# Car_0.net
KiCad netlist of a schematic drawn in EAGLE
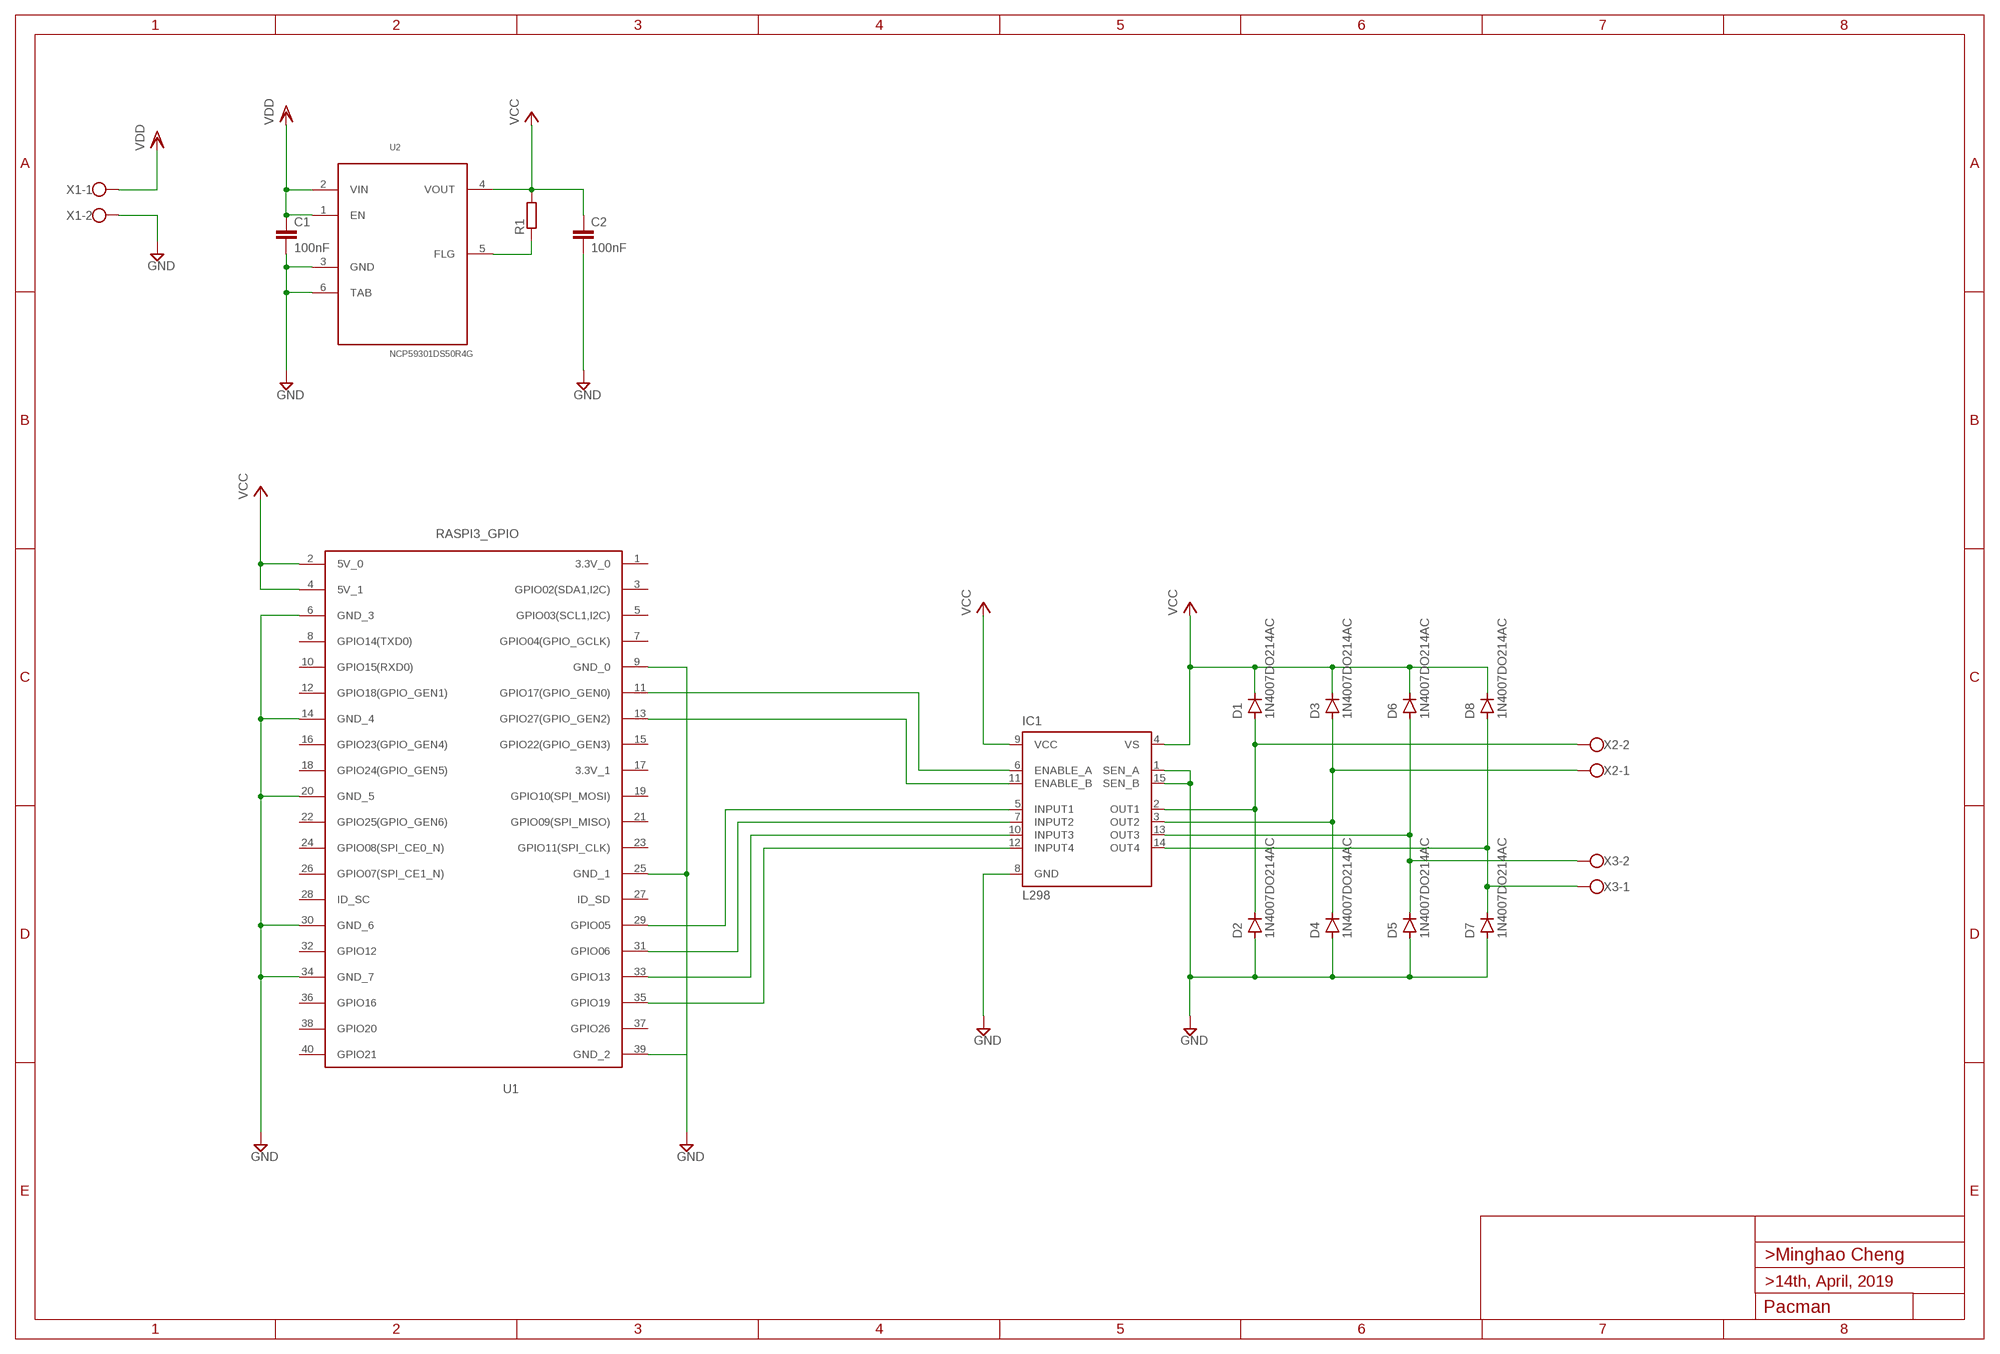
[diagram p0: schematic, sheet 1]

(export (version "E")
  (design (tool "Eeschema 10.0.6"))
  (components
    (comp (ref "C1")
      (value "100nF")
      (footprint "eagle-import:C0805")
      (libsource (lib "eagle-import") (part "C-EUC0805"))
    )
    (comp (ref "C2")
      (value "100nF")
      (footprint "eagle-import:C0805")
      (libsource (lib "eagle-import") (part "C-EUC0805"))
    )
    (comp (ref "D1")
      (value "1N4007DO214AC")
      (footprint "eagle-import:SMA-DO214AC")
      (libsource (lib "eagle-import") (part "1N4007DO214AC"))
    )
    (comp (ref "D2")
      (value "1N4007DO214AC")
      (footprint "eagle-import:SMA-DO214AC")
      (libsource (lib "eagle-import") (part "1N4007DO214AC"))
    )
    (comp (ref "D3")
      (value "1N4007DO214AC")
      (footprint "eagle-import:SMA-DO214AC")
      (libsource (lib "eagle-import") (part "1N4007DO214AC"))
    )
    (comp (ref "D4")
      (value "1N4007DO214AC")
      (footprint "eagle-import:SMA-DO214AC")
      (libsource (lib "eagle-import") (part "1N4007DO214AC"))
    )
    (comp (ref "D5")
      (value "1N4007DO214AC")
      (footprint "eagle-import:SMA-DO214AC")
      (libsource (lib "eagle-import") (part "1N4007DO214AC"))
    )
    (comp (ref "D6")
      (value "1N4007DO214AC")
      (footprint "eagle-import:SMA-DO214AC")
      (libsource (lib "eagle-import") (part "1N4007DO214AC"))
    )
    (comp (ref "D7")
      (value "1N4007DO214AC")
      (footprint "eagle-import:SMA-DO214AC")
      (libsource (lib "eagle-import") (part "1N4007DO214AC"))
    )
    (comp (ref "D8")
      (value "1N4007DO214AC")
      (footprint "eagle-import:SMA-DO214AC")
      (libsource (lib "eagle-import") (part "1N4007DO214AC"))
    )
    (comp (ref "IC1")
      (value "L298")
      (footprint "eagle-import:MULTIWATT-15")
      (fields (field (name "MPN") "L298N"))
      (libsource (lib "eagle-import") (part "L298"))
    )
    (comp (ref "R1")
      (value "R-EU_R0805")
      (footprint "eagle-import:R0805")
      (libsource (lib "eagle-import") (part "R-EU_R0805"))
    )
    (comp (ref "U1")
      (value "RASPI3_GPIO")
      (footprint "eagle-import:FE20-2")
      (libsource (lib "eagle-import") (part "RASPI3_GPIO"))
    )
    (comp (ref "U2")
      (value "NCP59301DS50R4G")
      (footprint "eagle-import:TO263-5")
      (libsource (lib "eagle-import") (part "NCP59301DS50R4G"))
    )
    (comp (ref "X1")
      (value "W237-102")
      (footprint "eagle-import:W237-102")
      (fields (field (name "MPN") "237-102"))
      (libsource (lib "eagle-import") (part "W237-102"))
    )
    (comp (ref "X2")
      (value "W237-102")
      (footprint "eagle-import:W237-102")
      (fields (field (name "MPN") "237-102"))
      (libsource (lib "eagle-import") (part "W237-102"))
    )
    (comp (ref "X3")
      (value "W237-102")
      (footprint "eagle-import:W237-102")
      (fields (field (name "MPN") "237-102"))
      (libsource (lib "eagle-import") (part "W237-102"))
    )
  )
  (nets
    (net (code "1") (name "GND") (class "Default")
      (node (ref "C1") (pin "2") (pinfunction "2_2") (pintype "passive"))
      (node (ref "C2") (pin "2") (pinfunction "2_2") (pintype "passive"))
      (node (ref "D2") (pin "A") (pinfunction "A_A") (pintype "passive"))
      (node (ref "D4") (pin "A") (pinfunction "A_A") (pintype "passive"))
      (node (ref "D5") (pin "A") (pinfunction "A_A") (pintype "passive"))
      (node (ref "D7") (pin "A") (pinfunction "A_A") (pintype "passive"))
      (node (ref "IC1") (pin "1") (pinfunction "SEN_A_1") (pintype "input"))
      (node (ref "IC1") (pin "15") (pinfunction "SEN_B_15") (pintype "input"))
      (node (ref "IC1") (pin "8") (pinfunction "GND_8") (pintype "power_in"))
      (node (ref "U1") (pin "14") (pinfunction "GND_4_14") (pintype "bidirectional"))
      (node (ref "U1") (pin "20") (pinfunction "GND_5_20") (pintype "bidirectional"))
      (node (ref "U1") (pin "25") (pinfunction "GND_1_25") (pintype "bidirectional"))
      (node (ref "U1") (pin "30") (pinfunction "GND_6_30") (pintype "bidirectional"))
      (node (ref "U1") (pin "34") (pinfunction "GND_7_34") (pintype "bidirectional"))
      (node (ref "U1") (pin "39") (pinfunction "GND_2_39") (pintype "bidirectional"))
      (node (ref "U1") (pin "6") (pinfunction "GND_3_6") (pintype "bidirectional"))
      (node (ref "U1") (pin "9") (pinfunction "GND_0_9") (pintype "bidirectional"))
      (node (ref "U2") (pin "3") (pinfunction "GND_3") (pintype "output"))
      (node (ref "U2") (pin "6") (pinfunction "TAB_6") (pintype "output"))
      (node (ref "X1") (pin "2") (pinfunction "KL_2") (pintype "passive"))
    )
    (net (code "2") (name "Net-(D2-C)") (class "Default")
      (node (ref "D1") (pin "A") (pinfunction "A_A") (pintype "passive"))
      (node (ref "D2") (pin "K") (pinfunction "C_K") (pintype "passive"))
      (node (ref "IC1") (pin "2") (pinfunction "OUT1_2") (pintype "output"))
      (node (ref "X2") (pin "2") (pinfunction "KL_2") (pintype "passive"))
    )
    (net (code "3") (name "Net-(D4-C)") (class "Default")
      (node (ref "D3") (pin "A") (pinfunction "A_A") (pintype "passive"))
      (node (ref "D4") (pin "K") (pinfunction "C_K") (pintype "passive"))
      (node (ref "IC1") (pin "3") (pinfunction "OUT2_3") (pintype "output"))
      (node (ref "X2") (pin "1") (pinfunction "KL_1") (pintype "passive"))
    )
    (net (code "4") (name "Net-(D5-C)") (class "Default")
      (node (ref "D5") (pin "K") (pinfunction "C_K") (pintype "passive"))
      (node (ref "D6") (pin "A") (pinfunction "A_A") (pintype "passive"))
      (node (ref "IC1") (pin "13") (pinfunction "OUT3_13") (pintype "output"))
      (node (ref "X3") (pin "2") (pinfunction "KL_2") (pintype "passive"))
    )
    (net (code "5") (name "Net-(D7-C)") (class "Default")
      (node (ref "D7") (pin "K") (pinfunction "C_K") (pintype "passive"))
      (node (ref "D8") (pin "A") (pinfunction "A_A") (pintype "passive"))
      (node (ref "IC1") (pin "14") (pinfunction "OUT4_14") (pintype "output"))
      (node (ref "X3") (pin "1") (pinfunction "KL_1") (pintype "passive"))
    )
    (net (code "6") (name "Net-(IC1-ENABLE_A)") (class "Default")
      (node (ref "IC1") (pin "6") (pinfunction "ENABLE_A_6") (pintype "input"))
      (node (ref "U1") (pin "11") (pinfunction "GPIO17(GPIO_GEN0)_11") (pintype "bidirectional"))
    )
    (net (code "7") (name "Net-(IC1-ENABLE_B)") (class "Default")
      (node (ref "IC1") (pin "11") (pinfunction "ENABLE_B_11") (pintype "input"))
      (node (ref "U1") (pin "13") (pinfunction "GPIO27(GPIO_GEN2)_13") (pintype "bidirectional"))
    )
    (net (code "8") (name "Net-(IC1-INPUT1)") (class "Default")
      (node (ref "IC1") (pin "5") (pinfunction "INPUT1_5") (pintype "input"))
      (node (ref "U1") (pin "29") (pinfunction "GPIO05_29") (pintype "bidirectional"))
    )
    (net (code "9") (name "Net-(IC1-INPUT2)") (class "Default")
      (node (ref "IC1") (pin "7") (pinfunction "INPUT2_7") (pintype "input"))
      (node (ref "U1") (pin "31") (pinfunction "GPIO06_31") (pintype "bidirectional"))
    )
    (net (code "10") (name "Net-(IC1-INPUT3)") (class "Default")
      (node (ref "IC1") (pin "10") (pinfunction "INPUT3_10") (pintype "input"))
      (node (ref "U1") (pin "33") (pinfunction "GPIO13_33") (pintype "bidirectional"))
    )
    (net (code "11") (name "Net-(IC1-INPUT4)") (class "Default")
      (node (ref "IC1") (pin "12") (pinfunction "INPUT4_12") (pintype "input"))
      (node (ref "U1") (pin "35") (pinfunction "GPIO19_35") (pintype "bidirectional"))
    )
    (net (code "12") (name "Net-(U2-FLG)") (class "Default")
      (node (ref "R1") (pin "1") (pinfunction "1_1") (pintype "passive"))
      (node (ref "U2") (pin "5") (pinfunction "FLG_5") (pintype "output"))
    )
    (net (code "13") (name "VCC") (class "Default")
      (node (ref "C2") (pin "1") (pinfunction "1_1") (pintype "passive"))
      (node (ref "D1") (pin "K") (pinfunction "C_K") (pintype "passive"))
      (node (ref "D3") (pin "K") (pinfunction "C_K") (pintype "passive"))
      (node (ref "D6") (pin "K") (pinfunction "C_K") (pintype "passive"))
      (node (ref "D8") (pin "K") (pinfunction "C_K") (pintype "passive"))
      (node (ref "IC1") (pin "4") (pinfunction "VS_4") (pintype "power_in"))
      (node (ref "IC1") (pin "9") (pinfunction "VCC_9") (pintype "power_in"))
      (node (ref "R1") (pin "2") (pinfunction "2_2") (pintype "passive"))
      (node (ref "U1") (pin "2") (pinfunction "5V_0_2") (pintype "bidirectional"))
      (node (ref "U1") (pin "4") (pinfunction "5V_1_4") (pintype "bidirectional"))
      (node (ref "U2") (pin "4") (pinfunction "VOUT_4") (pintype "output"))
    )
    (net (code "14") (name "VDD") (class "Default")
      (node (ref "C1") (pin "1") (pinfunction "1_1") (pintype "passive"))
      (node (ref "U2") (pin "1") (pinfunction "EN_1") (pintype "input"))
      (node (ref "U2") (pin "2") (pinfunction "VIN_2") (pintype "input"))
      (node (ref "X1") (pin "1") (pinfunction "KL_1") (pintype "passive"))
    )
    (net (code "15") (name "unconnected-(U1-3.3V_0-Pad1)") (class "Default")
      (node (ref "U1") (pin "1") (pinfunction "3.3V_0_1") (pintype "bidirectional"))
    )
    (net (code "16") (name "unconnected-(U1-3.3V_1-Pad17)") (class "Default")
      (node (ref "U1") (pin "17") (pinfunction "3.3V_1_17") (pintype "bidirectional"))
    )
    (net (code "17") (name "unconnected-(U1-GPIO02(SDA1,I2C)-Pad3)") (class "Default")
      (node (ref "U1") (pin "3") (pinfunction "GPIO02(SDA1,I2C)_3") (pintype "bidirectional"))
    )
    (net (code "18") (name "unconnected-(U1-GPIO03(SCL1,I2C)-Pad5)") (class "Default")
      (node (ref "U1") (pin "5") (pinfunction "GPIO03(SCL1,I2C)_5") (pintype "bidirectional"))
    )
    (net (code "19") (name "unconnected-(U1-GPIO04(GPIO_GCLK)-Pad7)") (class "Default")
      (node (ref "U1") (pin "7") (pinfunction "GPIO04(GPIO_GCLK)_7") (pintype "bidirectional"))
    )
    (net (code "20") (name "unconnected-(U1-GPIO07(SPI_CE1_N)-Pad26)") (class "Default")
      (node (ref "U1") (pin "26") (pinfunction "GPIO07(SPI_CE1_N)_26") (pintype "bidirectional"))
    )
    (net (code "21") (name "unconnected-(U1-GPIO08(SPI_CE0_N)-Pad24)") (class "Default")
      (node (ref "U1") (pin "24") (pinfunction "GPIO08(SPI_CE0_N)_24") (pintype "bidirectional"))
    )
    (net (code "22") (name "unconnected-(U1-GPIO09(SPI_MISO)-Pad21)") (class "Default")
      (node (ref "U1") (pin "21") (pinfunction "GPIO09(SPI_MISO)_21") (pintype "bidirectional"))
    )
    (net (code "23") (name "unconnected-(U1-GPIO10(SPI_MOSI)-Pad19)") (class "Default")
      (node (ref "U1") (pin "19") (pinfunction "GPIO10(SPI_MOSI)_19") (pintype "bidirectional"))
    )
    (net (code "24") (name "unconnected-(U1-GPIO11(SPI_CLK)-Pad23)") (class "Default")
      (node (ref "U1") (pin "23") (pinfunction "GPIO11(SPI_CLK)_23") (pintype "bidirectional"))
    )
    (net (code "25") (name "unconnected-(U1-GPIO12-Pad32)") (class "Default")
      (node (ref "U1") (pin "32") (pinfunction "GPIO12_32") (pintype "bidirectional"))
    )
    (net (code "26") (name "unconnected-(U1-GPIO14(TXD0)-Pad8)") (class "Default")
      (node (ref "U1") (pin "8") (pinfunction "GPIO14(TXD0)_8") (pintype "bidirectional"))
    )
    (net (code "27") (name "unconnected-(U1-GPIO15(RXD0)-Pad10)") (class "Default")
      (node (ref "U1") (pin "10") (pinfunction "GPIO15(RXD0)_10") (pintype "bidirectional"))
    )
    (net (code "28") (name "unconnected-(U1-GPIO16-Pad36)") (class "Default")
      (node (ref "U1") (pin "36") (pinfunction "GPIO16_36") (pintype "bidirectional"))
    )
    (net (code "29") (name "unconnected-(U1-GPIO18(GPIO_GEN1)-Pad12)") (class "Default")
      (node (ref "U1") (pin "12") (pinfunction "GPIO18(GPIO_GEN1)_12") (pintype "bidirectional"))
    )
    (net (code "30") (name "unconnected-(U1-GPIO20-Pad38)") (class "Default")
      (node (ref "U1") (pin "38") (pinfunction "GPIO20_38") (pintype "bidirectional"))
    )
    (net (code "31") (name "unconnected-(U1-GPIO21-Pad40)") (class "Default")
      (node (ref "U1") (pin "40") (pinfunction "GPIO21_40") (pintype "bidirectional"))
    )
    (net (code "32") (name "unconnected-(U1-GPIO22(GPIO_GEN3)-Pad15)") (class "Default")
      (node (ref "U1") (pin "15") (pinfunction "GPIO22(GPIO_GEN3)_15") (pintype "bidirectional"))
    )
    (net (code "33") (name "unconnected-(U1-GPIO23(GPIO_GEN4)-Pad16)") (class "Default")
      (node (ref "U1") (pin "16") (pinfunction "GPIO23(GPIO_GEN4)_16") (pintype "bidirectional"))
    )
    (net (code "34") (name "unconnected-(U1-GPIO24(GPIO_GEN5)-Pad18)") (class "Default")
      (node (ref "U1") (pin "18") (pinfunction "GPIO24(GPIO_GEN5)_18") (pintype "bidirectional"))
    )
    (net (code "35") (name "unconnected-(U1-GPIO25(GPIO_GEN6)-Pad22)") (class "Default")
      (node (ref "U1") (pin "22") (pinfunction "GPIO25(GPIO_GEN6)_22") (pintype "bidirectional"))
    )
    (net (code "36") (name "unconnected-(U1-GPIO26-Pad37)") (class "Default")
      (node (ref "U1") (pin "37") (pinfunction "GPIO26_37") (pintype "bidirectional"))
    )
    (net (code "37") (name "unconnected-(U1-ID_SC-Pad28)") (class "Default")
      (node (ref "U1") (pin "28") (pinfunction "ID_SC_28") (pintype "bidirectional"))
    )
    (net (code "38") (name "unconnected-(U1-ID_SD-Pad27)") (class "Default")
      (node (ref "U1") (pin "27") (pinfunction "ID_SD_27") (pintype "bidirectional"))
    )
  )
)
